# PowerStage.net
KiCad netlist of a schematic drawn in Altium Designer
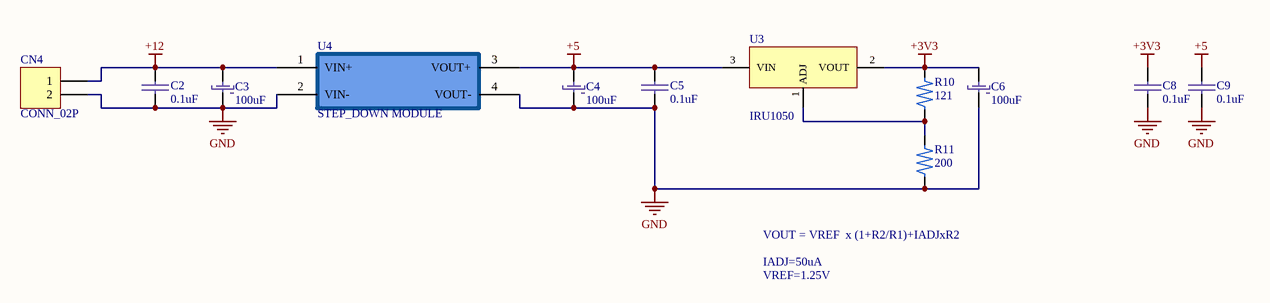
[diagram p0: PowerStage.SchDoc]

(export (version "E")
  (design (tool "Eeschema 10.0.6"))
  (components
    (comp (ref "C2")
      (value "0.1uF")
      (footprint "CAP_Axial_0.2mm")
      (description "Non-Polarized Capacitor")
      (libsource (lib "ProyectoTD3") (part "CAP_NP"))
    )
    (comp (ref "C3")
      (value "100uF")
      (footprint "C_RAD_11MM")
      (description "Polarized Capacitor")
      (libsource (lib "ProyectoTD3") (part "Cap_Pol"))
    )
    (comp (ref "C4")
      (value "100uF")
      (footprint "C_RAD_5mm")
      (description "Polarized Capacitor")
      (libsource (lib "ProyectoTD3") (part "Cap_Pol"))
    )
    (comp (ref "C5")
      (value "0.1uF")
      (footprint "CAP_Axial_0.2mm")
      (description "Non-Polarized Capacitor")
      (libsource (lib "ProyectoTD3") (part "CAP_NP"))
    )
    (comp (ref "C6")
      (value "100uF")
      (footprint "C_RAD_5mm")
      (description "Polarized Capacitor")
      (libsource (lib "ProyectoTD3") (part "Cap_Pol"))
    )
    (comp (ref "C8")
      (value "0.1uF")
      (footprint "CAP_Axial_0.2mm")
      (description "Non-Polarized Capacitor")
      (libsource (lib "ProyectoTD3") (part "CAP_NP"))
    )
    (comp (ref "C9")
      (value "0.1uF")
      (footprint "CAP_Axial_0.2mm")
      (description "Non-Polarized Capacitor")
      (libsource (lib "ProyectoTD3") (part "CAP_NP"))
    )
    (comp (ref "CN4")
      (value "CONN_02P")
      (footprint "TERMINAL_BLOCK_2_PIN")
      (description "Connector Generic 2 Vias")
      (libsource (lib "ProyectoTD3") (part "CONN_02P"))
    )
    (comp (ref "R10")
      (value "121")
      (footprint "RES_AXIAL_3.2_6MM")
      (description "Through-hole Resistor")
      (libsource (lib "ProyectoTD3") (part "RES"))
    )
    (comp (ref "R11")
      (value "200")
      (footprint "RES_AXIAL_3.2_6MM")
      (description "Through-hole Resistor")
      (libsource (lib "ProyectoTD3") (part "RES"))
    )
    (comp (ref "U3")
      (value "IRU1050")
      (footprint "IRU1050")
      (description "5A  LOW DROPOUT POSITIVEADJUSTABLE REGULATOR")
      (libsource (lib "ProyectoTD3") (part "IRU1050"))
    )
    (comp (ref "U4")
      (value "STEP_DOWN MODULE")
      (footprint "STEP_DOWN_MODULE")
      (libsource (lib "ProyectoTD3") (part "STEP_DOWN_MODULE"))
    )
  )
  (nets
    (net (code "1") (name "+3V3") (class "Default")
      (node (ref "C6") (pin "1") (pinfunction "1_1") (pintype "passive"))
      (node (ref "C8") (pin "1") (pinfunction "1_1") (pintype "passive"))
      (node (ref "R10") (pin "2") (pinfunction "*_2") (pintype "passive"))
      (node (ref "U3") (pin "2") (pinfunction "VOUT_2") (pintype "power_in"))
    )
    (net (code "2") (name "+5") (class "Default")
      (node (ref "C4") (pin "1") (pinfunction "1_1") (pintype "passive"))
      (node (ref "C5") (pin "1") (pinfunction "1_1") (pintype "passive"))
      (node (ref "C9") (pin "1") (pinfunction "1_1") (pintype "passive"))
      (node (ref "U3") (pin "3") (pinfunction "VIN_3") (pintype "power_in"))
      (node (ref "U4") (pin "3") (pinfunction "VOUT+_3") (pintype "passive"))
    )
    (net (code "3") (name "+12") (class "Default")
      (node (ref "C2") (pin "1") (pinfunction "1_1") (pintype "passive"))
      (node (ref "C3") (pin "1") (pinfunction "1_1") (pintype "passive"))
      (node (ref "CN4") (pin "1") (pinfunction "1_1") (pintype "passive"))
      (node (ref "U4") (pin "1") (pinfunction "VIN+_1") (pintype "passive"))
    )
    (net (code "4") (name "GND") (class "Default")
      (node (ref "C2") (pin "2") (pinfunction "2_2") (pintype "passive"))
      (node (ref "C3") (pin "2") (pinfunction "2_2") (pintype "passive"))
      (node (ref "C4") (pin "2") (pinfunction "2_2") (pintype "passive"))
      (node (ref "C5") (pin "2") (pinfunction "2_2") (pintype "passive"))
      (node (ref "C6") (pin "2") (pinfunction "2_2") (pintype "passive"))
      (node (ref "C8") (pin "2") (pinfunction "2_2") (pintype "passive"))
      (node (ref "C9") (pin "2") (pinfunction "2_2") (pintype "passive"))
      (node (ref "CN4") (pin "2") (pinfunction "2_2") (pintype "passive"))
      (node (ref "R11") (pin "1") (pinfunction "*_1") (pintype "passive"))
      (node (ref "U4") (pin "2") (pinfunction "VIN-_2") (pintype "passive"))
      (node (ref "U4") (pin "4") (pinfunction "VOUT-_4") (pintype "passive"))
    )
    (net (code "5") (name "Net-(U3-ADJ)") (class "Default")
      (node (ref "R10") (pin "1") (pinfunction "*_1") (pintype "passive"))
      (node (ref "R11") (pin "2") (pinfunction "*_2") (pintype "passive"))
      (node (ref "U3") (pin "1") (pinfunction "ADJ_1") (pintype "passive"))
    )
  )
)
